# WindStation.net
KiCad netlist of a schematic drawn in EAGLE
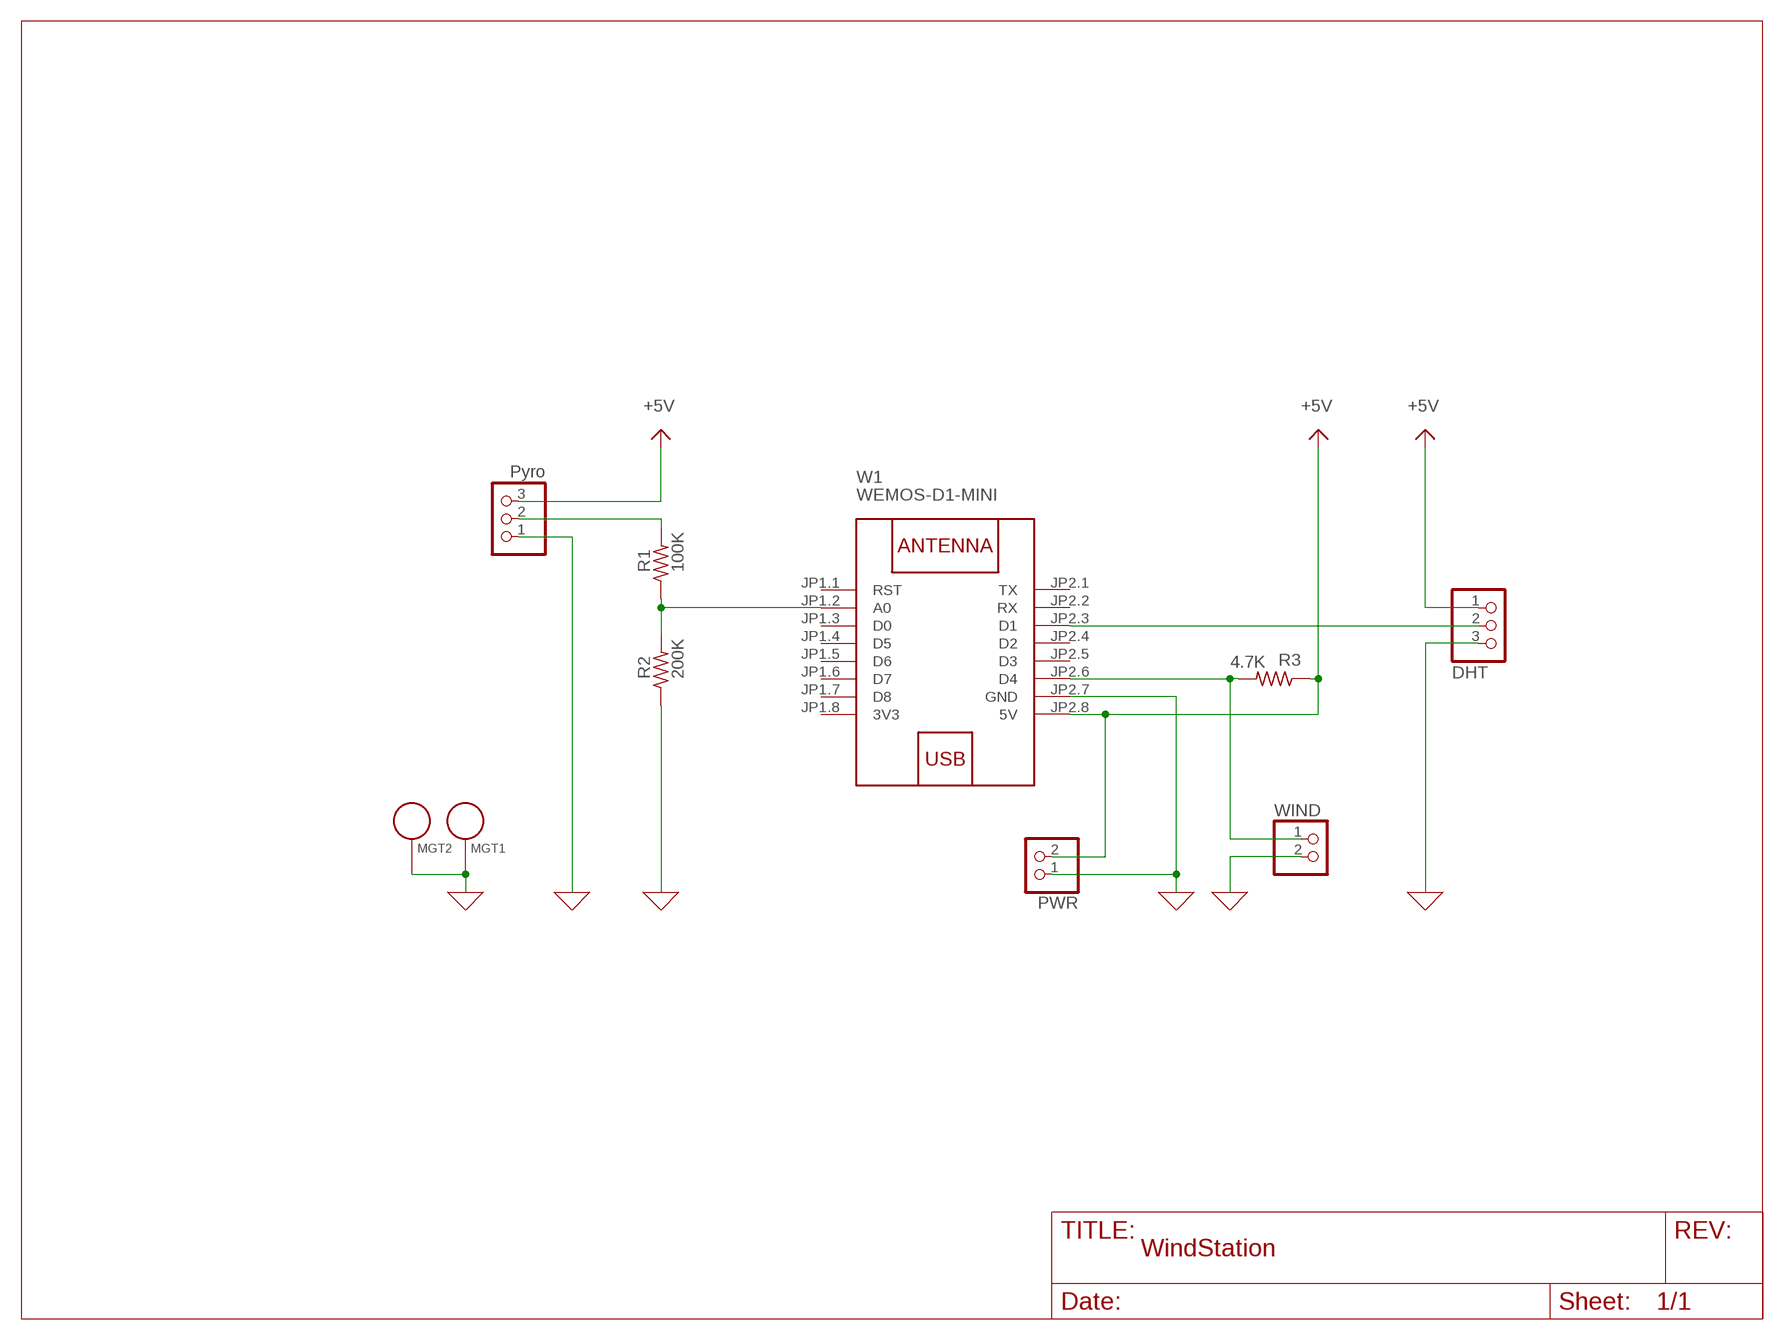
[diagram p0: schematic, sheet 1]

(export (version "E")
  (design (tool "Eeschema 10.0.6"))
  (components
    (comp (ref "DHT")
      (value "DHT")
      (footprint "eagle-import:1X03")
      (libsource (lib "eagle-import") (part "PINHD-1X3"))
    )
    (comp (ref "JP1")
      (value "Pyro")
      (footprint "eagle-import:1X03")
      (libsource (lib "eagle-import") (part "PINHD-1X3"))
    )
    (comp (ref "MGT1")
      (value "BEAGLEBONEBLACK_MOUNTING_HOLE")
      (footprint "eagle-import:BEAGLEBONEBLACK_MOUNTING_HOLE")
      (libsource (lib "eagle-import") (part "BEAGLEBONEBLACK_MOUNTING_HOLE"))
    )
    (comp (ref "MGT2")
      (value "BEAGLEBONEBLACK_MOUNTING_HOLE")
      (footprint "eagle-import:BEAGLEBONEBLACK_MOUNTING_HOLE")
      (libsource (lib "eagle-import") (part "BEAGLEBONEBLACK_MOUNTING_HOLE"))
    )
    (comp (ref "PWR")
      (value "PINHD-1X2")
      (footprint "eagle-import:1X02")
      (libsource (lib "eagle-import") (part "PINHD-1X2"))
    )
    (comp (ref "R1")
      (value "100K")
      (footprint "eagle-import:0207_10")
      (libsource (lib "eagle-import") (part "R-US_0207/10"))
    )
    (comp (ref "R2")
      (value "200K")
      (footprint "eagle-import:0207_10")
      (libsource (lib "eagle-import") (part "R-US_0207/10"))
    )
    (comp (ref "R3")
      (value "4.7K")
      (footprint "eagle-import:0207_10")
      (libsource (lib "eagle-import") (part "R-US_0207/10"))
    )
    (comp (ref "W1")
      (value "WEMOS-D1-MINI")
      (footprint "eagle-import:WEMOS-D1-MINI")
      (libsource (lib "eagle-import") (part "WEMOS-D1-MINI"))
    )
    (comp (ref "WIND")
      (value "PINHD-1X2")
      (footprint "eagle-import:1X02")
      (libsource (lib "eagle-import") (part "PINHD-1X2"))
    )
  )
  (nets
    (net (code "1") (name "/3V3") (class "Default")
      (node (ref "W1") (pin "JP1.8") (pinfunction "3V3_JP1.8") (pintype "power_in"))
    )
    (net (code "2") (name "GND") (class "Default")
      (node (ref "DHT") (pin "3") (pinfunction "3_3") (pintype "passive"))
      (node (ref "JP1") (pin "1") (pinfunction "1_1") (pintype "passive"))
      (node (ref "MGT1") (pin "P$1") (pinfunction "P$1_P$1") (pintype "bidirectional"))
      (node (ref "MGT2") (pin "P$1") (pinfunction "P$1_P$1") (pintype "bidirectional"))
      (node (ref "PWR") (pin "1") (pinfunction "1_1") (pintype "passive"))
      (node (ref "R2") (pin "1") (pinfunction "1_1") (pintype "passive"))
      (node (ref "W1") (pin "JP2.7") (pinfunction "GND_JP2.7") (pintype "power_in"))
      (node (ref "WIND") (pin "2") (pinfunction "2_2") (pintype "passive"))
    )
    (net (code "3") (name "Net-(JP1-Pad2)") (class "Default")
      (node (ref "JP1") (pin "2") (pinfunction "2_2") (pintype "passive"))
      (node (ref "R1") (pin "2") (pinfunction "2_2") (pintype "passive"))
    )
    (net (code "4") (name "Net-(W1-A0)") (class "Default")
      (node (ref "R1") (pin "1") (pinfunction "1_1") (pintype "passive"))
      (node (ref "R2") (pin "2") (pinfunction "2_2") (pintype "passive"))
      (node (ref "W1") (pin "JP1.2") (pinfunction "A0_JP1.2") (pintype "bidirectional"))
    )
    (net (code "5") (name "Net-(W1-D1)") (class "Default")
      (node (ref "DHT") (pin "2") (pinfunction "2_2") (pintype "passive"))
      (node (ref "W1") (pin "JP2.3") (pinfunction "D1_JP2.3") (pintype "bidirectional"))
    )
    (net (code "6") (name "Net-(W1-D4)") (class "Default")
      (node (ref "R3") (pin "2") (pinfunction "2_2") (pintype "passive"))
      (node (ref "W1") (pin "JP2.6") (pinfunction "D4_JP2.6") (pintype "bidirectional"))
      (node (ref "WIND") (pin "1") (pinfunction "1_1") (pintype "passive"))
    )
    (net (code "7") (name "VCC") (class "Default")
      (node (ref "DHT") (pin "1") (pinfunction "1_1") (pintype "passive"))
      (node (ref "JP1") (pin "3") (pinfunction "3_3") (pintype "passive"))
      (node (ref "PWR") (pin "2") (pinfunction "2_2") (pintype "passive"))
      (node (ref "R3") (pin "1") (pinfunction "1_1") (pintype "passive"))
      (node (ref "W1") (pin "JP2.8") (pinfunction "5V_JP2.8") (pintype "power_in"))
    )
    (net (code "8") (name "unconnected-(W1-D0-PadJP1.3)") (class "Default")
      (node (ref "W1") (pin "JP1.3") (pinfunction "D0_JP1.3") (pintype "bidirectional"))
    )
    (net (code "9") (name "unconnected-(W1-D2-PadJP2.4)") (class "Default")
      (node (ref "W1") (pin "JP2.4") (pinfunction "D2_JP2.4") (pintype "bidirectional"))
    )
    (net (code "10") (name "unconnected-(W1-D3-PadJP2.5)") (class "Default")
      (node (ref "W1") (pin "JP2.5") (pinfunction "D3_JP2.5") (pintype "bidirectional"))
    )
    (net (code "11") (name "unconnected-(W1-D5-PadJP1.4)") (class "Default")
      (node (ref "W1") (pin "JP1.4") (pinfunction "D5_JP1.4") (pintype "bidirectional"))
    )
    (net (code "12") (name "unconnected-(W1-D6-PadJP1.5)") (class "Default")
      (node (ref "W1") (pin "JP1.5") (pinfunction "D6_JP1.5") (pintype "bidirectional"))
    )
    (net (code "13") (name "unconnected-(W1-D7-PadJP1.6)") (class "Default")
      (node (ref "W1") (pin "JP1.6") (pinfunction "D7_JP1.6") (pintype "bidirectional"))
    )
    (net (code "14") (name "unconnected-(W1-D8-PadJP1.7)") (class "Default")
      (node (ref "W1") (pin "JP1.7") (pinfunction "D8_JP1.7") (pintype "bidirectional"))
    )
    (net (code "15") (name "unconnected-(W1-RST-PadJP1.1)") (class "Default")
      (node (ref "W1") (pin "JP1.1") (pinfunction "RST_JP1.1") (pintype "bidirectional"))
    )
    (net (code "16") (name "unconnected-(W1-RX-PadJP2.2)") (class "Default")
      (node (ref "W1") (pin "JP2.2") (pinfunction "RX_JP2.2") (pintype "bidirectional"))
    )
    (net (code "17") (name "unconnected-(W1-TX-PadJP2.1)") (class "Default")
      (node (ref "W1") (pin "JP2.1") (pinfunction "TX_JP2.1") (pintype "bidirectional"))
    )
  )
)
